# TapTempoMini.net
KiCad netlist of a schematic drawn in EAGLE
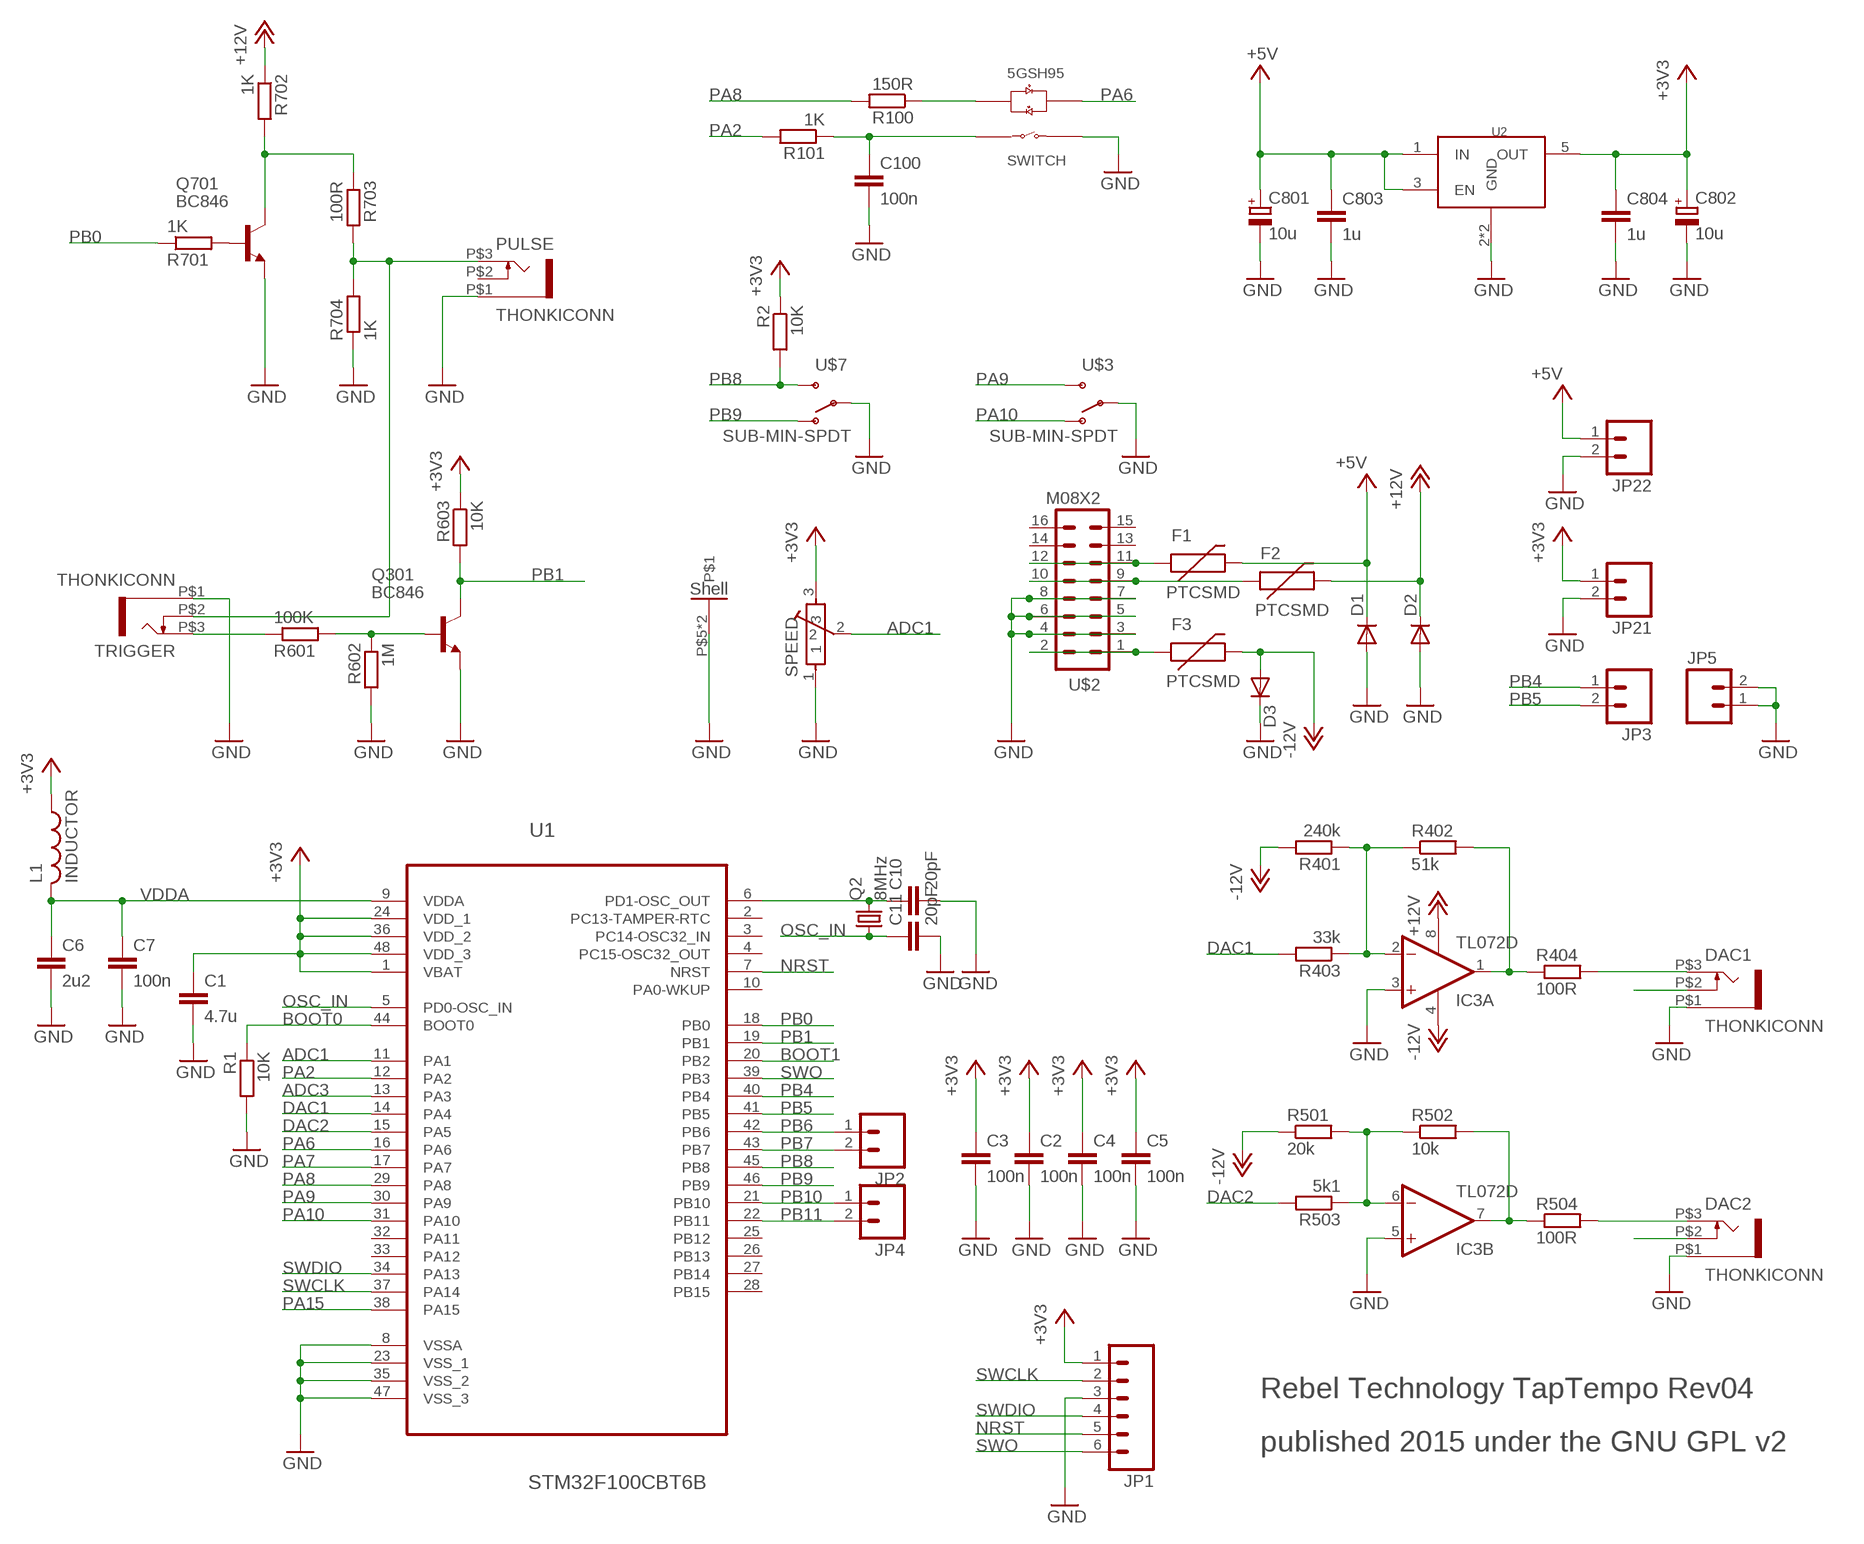
[diagram p0: schematic, sheet 1]

(export (version "E")
  (design (tool "Eeschema 10.0.6"))
  (components
    (comp (ref "C1")
      (value "4.7u")
      (footprint "eagle-import:C0603")
      (libsource (lib "eagle-import") (part "C-EUC0603"))
    )
    (comp (ref "C2")
      (value "100n")
      (footprint "eagle-import:C0603")
      (libsource (lib "eagle-import") (part "C-EUC0603"))
    )
    (comp (ref "C3")
      (value "100n")
      (footprint "eagle-import:C0603")
      (libsource (lib "eagle-import") (part "C-EUC0603"))
    )
    (comp (ref "C4")
      (value "100n")
      (footprint "eagle-import:C0603")
      (libsource (lib "eagle-import") (part "C-EUC0603"))
    )
    (comp (ref "C5")
      (value "100n")
      (footprint "eagle-import:C0603")
      (libsource (lib "eagle-import") (part "C-EUC0603"))
    )
    (comp (ref "C6")
      (value "2u2")
      (footprint "eagle-import:C0603")
      (libsource (lib "eagle-import") (part "C-EUC0603"))
    )
    (comp (ref "C7")
      (value "100n")
      (footprint "eagle-import:C0603")
      (libsource (lib "eagle-import") (part "C-EUC0603"))
    )
    (comp (ref "C10")
      (value "20pF")
      (footprint "eagle-import:C0603")
      (libsource (lib "eagle-import") (part "C-EUC0603"))
    )
    (comp (ref "C11")
      (value "20pF")
      (footprint "eagle-import:C0603")
      (libsource (lib "eagle-import") (part "C-EUC0603"))
    )
    (comp (ref "C100")
      (value "100n")
      (footprint "eagle-import:C0603")
      (libsource (lib "eagle-import") (part "C-EUC0603"))
    )
    (comp (ref "C801")
      (value "10u")
      (footprint "eagle-import:SANYO-OSCON_SMD_A5")
      (libsource (lib "eagle-import") (part "CPOL-EUSANYO_SMD_A5"))
    )
    (comp (ref "C802")
      (value "10u")
      (footprint "eagle-import:SANYO-OSCON_SMD_A5")
      (libsource (lib "eagle-import") (part "CPOL-EUSANYO_SMD_A5"))
    )
    (comp (ref "C803")
      (value "1u")
      (footprint "eagle-import:C0603")
      (libsource (lib "eagle-import") (part "C-EUC0603"))
    )
    (comp (ref "C804")
      (value "1u")
      (footprint "eagle-import:C0603")
      (libsource (lib "eagle-import") (part "C-EUC0603"))
    )
    (comp (ref "D1")
      (value "DIODESMA")
      (footprint "eagle-import:SMA-DIODE")
      (libsource (lib "eagle-import") (part "DIODESMA"))
    )
    (comp (ref "D2")
      (value "DIODESMA")
      (footprint "eagle-import:SMA-DIODE")
      (libsource (lib "eagle-import") (part "DIODESMA"))
    )
    (comp (ref "D3")
      (value "DIODESMA")
      (footprint "eagle-import:SMA-DIODE")
      (libsource (lib "eagle-import") (part "DIODESMA"))
    )
    (comp (ref "DAC1")
      (value "THONKICONN")
      (footprint "eagle-import:THONKICONN")
      (libsource (lib "eagle-import") (part "THONKICONN"))
    )
    (comp (ref "DAC2")
      (value "THONKICONN")
      (footprint "eagle-import:THONKICONN")
      (libsource (lib "eagle-import") (part "THONKICONN"))
    )
    (comp (ref "F1")
      (value "PTCSMD")
      (footprint "eagle-import:PTC-1206")
      (libsource (lib "eagle-import") (part "PTCSMD"))
    )
    (comp (ref "F2")
      (value "PTCSMD")
      (footprint "eagle-import:PTC-1206")
      (libsource (lib "eagle-import") (part "PTCSMD"))
    )
    (comp (ref "F3")
      (value "PTCSMD")
      (footprint "eagle-import:PTC-1206")
      (libsource (lib "eagle-import") (part "PTCSMD"))
    )
    (comp (ref "IC3")
      (value "TL072D")
      (footprint "eagle-import:SO08")
      (libsource (lib "eagle-import") (part "TL072D"))
    )
    (comp (ref "JP1")
      (value "M06SIP")
      (footprint "eagle-import:1X06")
      (libsource (lib "eagle-import") (part "M06SIP"))
    )
    (comp (ref "JP2")
      (value "M02PTH")
      (footprint "eagle-import:1X02")
      (libsource (lib "eagle-import") (part "M02PTH"))
    )
    (comp (ref "JP3")
      (value "M02PTH")
      (footprint "eagle-import:1X02")
      (libsource (lib "eagle-import") (part "M02PTH"))
    )
    (comp (ref "JP4")
      (value "M02PTH")
      (footprint "eagle-import:1X02")
      (libsource (lib "eagle-import") (part "M02PTH"))
    )
    (comp (ref "JP5")
      (value "M02PTH")
      (footprint "eagle-import:1X02")
      (libsource (lib "eagle-import") (part "M02PTH"))
    )
    (comp (ref "JP21")
      (value "M02PTH")
      (footprint "eagle-import:1X02")
      (libsource (lib "eagle-import") (part "M02PTH"))
    )
    (comp (ref "JP22")
      (value "M02PTH")
      (footprint "eagle-import:1X02")
      (libsource (lib "eagle-import") (part "M02PTH"))
    )
    (comp (ref "L1")
      (value "INDUCTOR")
      (footprint "eagle-import:0603")
      (libsource (lib "eagle-import") (part "INDUCTOR"))
    )
    (comp (ref "PULSE")
      (value "THONKICONN")
      (footprint "eagle-import:THONKICONN")
      (libsource (lib "eagle-import") (part "THONKICONN"))
    )
    (comp (ref "Q2")
      (value "8MHz")
      (footprint "eagle-import:HC49UP")
      (libsource (lib "eagle-import") (part "CRYSTALHC49UP"))
    )
    (comp (ref "Q301")
      (value "BC846")
      (footprint "eagle-import:SOT23")
      (libsource (lib "eagle-import") (part "BC846"))
    )
    (comp (ref "Q701")
      (value "BC846")
      (footprint "eagle-import:SOT23")
      (libsource (lib "eagle-import") (part "BC846"))
    )
    (comp (ref "R1")
      (value "10K")
      (footprint "eagle-import:R0603")
      (libsource (lib "eagle-import") (part "R-EU_R0603"))
    )
    (comp (ref "R2")
      (value "10K")
      (footprint "eagle-import:R0603")
      (libsource (lib "eagle-import") (part "R-EU_R0603"))
    )
    (comp (ref "R100")
      (value "150R")
      (footprint "eagle-import:0603")
      (libsource (lib "eagle-import") (part "R-EU_0603"))
    )
    (comp (ref "R101")
      (value "1K")
      (footprint "eagle-import:R0603")
      (libsource (lib "eagle-import") (part "R-EU_R0603"))
    )
    (comp (ref "R401")
      (value "240k")
      (footprint "eagle-import:R0603")
      (libsource (lib "eagle-import") (part "R-EU_R0603"))
    )
    (comp (ref "R402")
      (value "51k")
      (footprint "eagle-import:R0603")
      (libsource (lib "eagle-import") (part "R-EU_R0603"))
    )
    (comp (ref "R403")
      (value "33k")
      (footprint "eagle-import:R0603")
      (libsource (lib "eagle-import") (part "R-EU_R0603"))
    )
    (comp (ref "R404")
      (value "100R")
      (footprint "eagle-import:R0603")
      (libsource (lib "eagle-import") (part "R-EU_R0603"))
    )
    (comp (ref "R501")
      (value "20k")
      (footprint "eagle-import:R0603")
      (libsource (lib "eagle-import") (part "R-EU_R0603"))
    )
    (comp (ref "R502")
      (value "10k")
      (footprint "eagle-import:R0603")
      (libsource (lib "eagle-import") (part "R-EU_R0603"))
    )
    (comp (ref "R503")
      (value "5k1")
      (footprint "eagle-import:R0603")
      (libsource (lib "eagle-import") (part "R-EU_R0603"))
    )
    (comp (ref "R504")
      (value "100R")
      (footprint "eagle-import:R0603")
      (libsource (lib "eagle-import") (part "R-EU_R0603"))
    )
    (comp (ref "R601")
      (value "100K")
      (footprint "eagle-import:R0603")
      (libsource (lib "eagle-import") (part "R-EU_R0603"))
    )
    (comp (ref "R602")
      (value "1M")
      (footprint "eagle-import:R0603")
      (libsource (lib "eagle-import") (part "R-EU_R0603"))
    )
    (comp (ref "R603")
      (value "10K")
      (footprint "eagle-import:R0603")
      (libsource (lib "eagle-import") (part "R-EU_R0603"))
    )
    (comp (ref "R701")
      (value "1K")
      (footprint "eagle-import:R0603")
      (libsource (lib "eagle-import") (part "R-EU_R0603"))
    )
    (comp (ref "R702")
      (value "1K")
      (footprint "eagle-import:R0603")
      (libsource (lib "eagle-import") (part "R-EU_R0603"))
    )
    (comp (ref "R703")
      (value "100R")
      (footprint "eagle-import:R0603")
      (libsource (lib "eagle-import") (part "R-EU_R0603"))
    )
    (comp (ref "R704")
      (value "1K")
      (footprint "eagle-import:R0603")
      (libsource (lib "eagle-import") (part "R-EU_R0603"))
    )
    (comp (ref "SPEED")
      (value "POT-ALPS-RK09L1140")
      (footprint "eagle-import:POT-ALPS-RK09L1140")
      (libsource (lib "eagle-import") (part "POT-ALPS-RK09L1140"))
    )
    (comp (ref "TRIGGER")
      (value "THONKICONN")
      (footprint "eagle-import:THONKICONN")
      (libsource (lib "eagle-import") (part "THONKICONN"))
    )
    (comp (ref "U$1")
      (value "5GTH9")
      (footprint "eagle-import:5GTH9")
      (libsource (lib "eagle-import") (part "5GTH9"))
    )
    (comp (ref "U$2")
      (value "M08X2")
      (footprint "eagle-import:2X8")
      (libsource (lib "eagle-import") (part "M08X2"))
    )
    (comp (ref "U$3")
      (value "SUB-MIN-SPDT")
      (footprint "eagle-import:SUB-MIN-SPDT")
      (libsource (lib "eagle-import") (part "SUB-MIN-SPDT"))
    )
    (comp (ref "U$7")
      (value "SUB-MIN-SPDT")
      (footprint "eagle-import:SUB-MIN-SPDT")
      (libsource (lib "eagle-import") (part "SUB-MIN-SPDT"))
    )
    (comp (ref "U1")
      (value "STM32F100CBT6B")
      (footprint "eagle-import:QFP50P900X900X160-48N")
      (libsource (lib "eagle-import") (part "STM32F100CBT6B"))
    )
    (comp (ref "U2")
      (value "NCP702")
      (footprint "eagle-import:TSOP-5")
      (libsource (lib "eagle-import") (part "NCP702"))
    )
  )
  (nets
    (net (code "1") (name "+3V3") (class "Default")
      (node (ref "C1") (pin "1") (pinfunction "1_1") (pintype "passive"))
      (node (ref "C2") (pin "1") (pinfunction "1_1") (pintype "passive"))
      (node (ref "C3") (pin "1") (pinfunction "1_1") (pintype "passive"))
      (node (ref "C4") (pin "1") (pinfunction "1_1") (pintype "passive"))
      (node (ref "C5") (pin "1") (pinfunction "1_1") (pintype "passive"))
      (node (ref "C802") (pin "+") (pinfunction "+_+") (pintype "passive"))
      (node (ref "C804") (pin "1") (pinfunction "1_1") (pintype "passive"))
      (node (ref "JP1") (pin "1") (pinfunction "1_1") (pintype "passive"))
      (node (ref "JP21") (pin "1") (pinfunction "1_1") (pintype "passive"))
      (node (ref "L1") (pin "1") (pinfunction "1_1") (pintype "passive"))
      (node (ref "R2") (pin "1") (pinfunction "1_1") (pintype "passive"))
      (node (ref "R603") (pin "1") (pinfunction "1_1") (pintype "passive"))
      (node (ref "SPEED") (pin "3") (pinfunction "3_3") (pintype "bidirectional"))
      (node (ref "U1") (pin "1") (pinfunction "VBAT_1") (pintype "power_in"))
      (node (ref "U1") (pin "24") (pinfunction "VDD_1_24") (pintype "power_in"))
      (node (ref "U1") (pin "36") (pinfunction "VDD_2_36") (pintype "power_in"))
      (node (ref "U1") (pin "48") (pinfunction "VDD_3_48") (pintype "power_in"))
      (node (ref "U2") (pin "5") (pinfunction "OUT_5") (pintype "bidirectional"))
    )
    (net (code "2") (name "+5V") (class "Default")
      (node (ref "C801") (pin "+") (pinfunction "+_+") (pintype "passive"))
      (node (ref "C803") (pin "1") (pinfunction "1_1") (pintype "passive"))
      (node (ref "D1") (pin "C") (pinfunction "C_C") (pintype "passive"))
      (node (ref "F1") (pin "2") (pinfunction "2_2") (pintype "bidirectional"))
      (node (ref "JP22") (pin "1") (pinfunction "1_1") (pintype "passive"))
      (node (ref "U2") (pin "1") (pinfunction "IN_1") (pintype "bidirectional"))
      (node (ref "U2") (pin "3") (pinfunction "EN_3") (pintype "bidirectional"))
    )
    (net (code "3") (name "+12V") (class "Default")
      (node (ref "D2") (pin "C") (pinfunction "C_C") (pintype "passive"))
      (node (ref "F2") (pin "2") (pinfunction "2_2") (pintype "bidirectional"))
      (node (ref "IC3") (pin "8") (pinfunction "V+_8") (pintype "power_in"))
      (node (ref "R702") (pin "1") (pinfunction "1_1") (pintype "passive"))
    )
    (net (code "4") (name "-12V") (class "Default")
      (node (ref "D3") (pin "A") (pinfunction "A_A") (pintype "passive"))
      (node (ref "F3") (pin "2") (pinfunction "2_2") (pintype "bidirectional"))
      (node (ref "IC3") (pin "4") (pinfunction "V-_4") (pintype "power_in"))
      (node (ref "R401") (pin "2") (pinfunction "2_2") (pintype "passive"))
      (node (ref "R501") (pin "1") (pinfunction "1_1") (pintype "passive"))
    )
    (net (code "5") (name "/ADC1") (class "Default")
      (node (ref "SPEED") (pin "2") (pinfunction "2_2") (pintype "bidirectional"))
      (node (ref "U1") (pin "11") (pinfunction "PA1_11") (pintype "bidirectional"))
    )
    (net (code "6") (name "/ADC3") (class "Default")
      (node (ref "U1") (pin "13") (pinfunction "PA3_13") (pintype "bidirectional"))
    )
    (net (code "7") (name "/BOOT0") (class "Default")
      (node (ref "R1") (pin "1") (pinfunction "1_1") (pintype "passive"))
      (node (ref "U1") (pin "44") (pinfunction "BOOT0_44") (pintype "input"))
    )
    (net (code "8") (name "/BOOT1") (class "Default")
      (node (ref "U1") (pin "20") (pinfunction "PB2_20") (pintype "bidirectional"))
    )
    (net (code "9") (name "/DAC1") (class "Default")
      (node (ref "R403") (pin "2") (pinfunction "2_2") (pintype "passive"))
      (node (ref "U1") (pin "14") (pinfunction "PA4_14") (pintype "bidirectional"))
    )
    (net (code "10") (name "/DAC2") (class "Default")
      (node (ref "R503") (pin "2") (pinfunction "2_2") (pintype "passive"))
      (node (ref "U1") (pin "15") (pinfunction "PA5_15") (pintype "bidirectional"))
    )
    (net (code "11") (name "/NRST") (class "Default")
      (node (ref "JP1") (pin "5") (pinfunction "5_5") (pintype "passive"))
      (node (ref "U1") (pin "7") (pinfunction "NRST_7") (pintype "bidirectional"))
    )
    (net (code "12") (name "/OSC_IN") (class "Default")
      (node (ref "C11") (pin "1") (pinfunction "1_1") (pintype "passive"))
      (node (ref "Q2") (pin "1") (pinfunction "1_1") (pintype "passive"))
      (node (ref "U1") (pin "5") (pinfunction "PD0-OSC_IN_5") (pintype "input"))
    )
    (net (code "13") (name "/PA2") (class "Default")
      (node (ref "R101") (pin "2") (pinfunction "2_2") (pintype "passive"))
      (node (ref "U1") (pin "12") (pinfunction "PA2_12") (pintype "bidirectional"))
    )
    (net (code "14") (name "/PA6") (class "Default")
      (node (ref "U$1") (pin "+3") (pinfunction "LED_R+_+3") (pintype "input"))
      (node (ref "U1") (pin "16") (pinfunction "PA6_16") (pintype "bidirectional"))
    )
    (net (code "15") (name "/PA7") (class "Default")
      (node (ref "U1") (pin "17") (pinfunction "PA7_17") (pintype "bidirectional"))
    )
    (net (code "16") (name "/PA8") (class "Default")
      (node (ref "R100") (pin "2") (pinfunction "2_2") (pintype "passive"))
      (node (ref "U1") (pin "29") (pinfunction "PA8_29") (pintype "bidirectional"))
    )
    (net (code "17") (name "/PA9") (class "Default")
      (node (ref "U$3") (pin "3") (pinfunction "S_3") (pintype "passive"))
      (node (ref "U1") (pin "30") (pinfunction "PA9_30") (pintype "bidirectional"))
    )
    (net (code "18") (name "/PA10") (class "Default")
      (node (ref "U$3") (pin "1") (pinfunction "O_1") (pintype "passive"))
      (node (ref "U1") (pin "31") (pinfunction "PA10_31") (pintype "bidirectional"))
    )
    (net (code "19") (name "/PA15") (class "Default")
      (node (ref "U1") (pin "38") (pinfunction "PA15_38") (pintype "bidirectional"))
    )
    (net (code "20") (name "/PB0") (class "Default")
      (node (ref "R701") (pin "1") (pinfunction "1_1") (pintype "passive"))
      (node (ref "U1") (pin "18") (pinfunction "PB0_18") (pintype "bidirectional"))
    )
    (net (code "21") (name "/PB1") (class "Default")
      (node (ref "Q301") (pin "3") (pinfunction "C_3") (pintype "passive"))
      (node (ref "R603") (pin "2") (pinfunction "2_2") (pintype "passive"))
      (node (ref "U1") (pin "19") (pinfunction "PB1_19") (pintype "bidirectional"))
    )
    (net (code "22") (name "/PB4") (class "Default")
      (node (ref "JP3") (pin "1") (pinfunction "1_1") (pintype "passive"))
      (node (ref "U1") (pin "40") (pinfunction "PB4_40") (pintype "bidirectional"))
    )
    (net (code "23") (name "/PB5") (class "Default")
      (node (ref "JP3") (pin "2") (pinfunction "2_2") (pintype "passive"))
      (node (ref "U1") (pin "41") (pinfunction "PB5_41") (pintype "bidirectional"))
    )
    (net (code "24") (name "/PB6") (class "Default")
      (node (ref "JP2") (pin "1") (pinfunction "1_1") (pintype "passive"))
      (node (ref "U1") (pin "42") (pinfunction "PB6_42") (pintype "bidirectional"))
    )
    (net (code "25") (name "/PB7") (class "Default")
      (node (ref "JP2") (pin "2") (pinfunction "2_2") (pintype "passive"))
      (node (ref "U1") (pin "43") (pinfunction "PB7_43") (pintype "bidirectional"))
    )
    (net (code "26") (name "/PB8") (class "Default")
      (node (ref "R2") (pin "2") (pinfunction "2_2") (pintype "passive"))
      (node (ref "U$7") (pin "3") (pinfunction "S_3") (pintype "passive"))
      (node (ref "U1") (pin "45") (pinfunction "PB8_45") (pintype "bidirectional"))
    )
    (net (code "27") (name "/PB9") (class "Default")
      (node (ref "U$7") (pin "1") (pinfunction "O_1") (pintype "passive"))
      (node (ref "U1") (pin "46") (pinfunction "PB9_46") (pintype "bidirectional"))
    )
    (net (code "28") (name "/PB10") (class "Default")
      (node (ref "JP4") (pin "1") (pinfunction "1_1") (pintype "passive"))
      (node (ref "U1") (pin "21") (pinfunction "PB10_21") (pintype "bidirectional"))
    )
    (net (code "29") (name "/PB11") (class "Default")
      (node (ref "JP4") (pin "2") (pinfunction "2_2") (pintype "passive"))
      (node (ref "U1") (pin "22") (pinfunction "PB11_22") (pintype "bidirectional"))
    )
    (net (code "30") (name "/SWCLK") (class "Default")
      (node (ref "JP1") (pin "2") (pinfunction "2_2") (pintype "passive"))
      (node (ref "U1") (pin "37") (pinfunction "PA14_37") (pintype "bidirectional"))
    )
    (net (code "31") (name "/SWDIO") (class "Default")
      (node (ref "JP1") (pin "4") (pinfunction "4_4") (pintype "passive"))
      (node (ref "U1") (pin "34") (pinfunction "PA13_34") (pintype "bidirectional"))
    )
    (net (code "32") (name "/SWO") (class "Default")
      (node (ref "JP1") (pin "6") (pinfunction "6_6") (pintype "passive"))
      (node (ref "U1") (pin "39") (pinfunction "PB3_39") (pintype "bidirectional"))
    )
    (net (code "33") (name "/VDDA") (class "Default")
      (node (ref "C6") (pin "1") (pinfunction "1_1") (pintype "passive"))
      (node (ref "C7") (pin "1") (pinfunction "1_1") (pintype "passive"))
      (node (ref "L1") (pin "2") (pinfunction "2_2") (pintype "passive"))
      (node (ref "U1") (pin "9") (pinfunction "VDDA_9") (pintype "power_in"))
    )
    (net (code "34") (name "GND") (class "Default")
      (node (ref "C1") (pin "2") (pinfunction "2_2") (pintype "passive"))
      (node (ref "C10") (pin "2") (pinfunction "2_2") (pintype "passive"))
      (node (ref "C100") (pin "2") (pinfunction "2_2") (pintype "passive"))
      (node (ref "C11") (pin "2") (pinfunction "2_2") (pintype "passive"))
      (node (ref "C2") (pin "2") (pinfunction "2_2") (pintype "passive"))
      (node (ref "C3") (pin "2") (pinfunction "2_2") (pintype "passive"))
      (node (ref "C4") (pin "2") (pinfunction "2_2") (pintype "passive"))
      (node (ref "C5") (pin "2") (pinfunction "2_2") (pintype "passive"))
      (node (ref "C6") (pin "2") (pinfunction "2_2") (pintype "passive"))
      (node (ref "C7") (pin "2") (pinfunction "2_2") (pintype "passive"))
      (node (ref "C801") (pin "-") (pinfunction "-_-") (pintype "passive"))
      (node (ref "C802") (pin "-") (pinfunction "-_-") (pintype "passive"))
      (node (ref "C803") (pin "2") (pinfunction "2_2") (pintype "passive"))
      (node (ref "C804") (pin "2") (pinfunction "2_2") (pintype "passive"))
      (node (ref "D1") (pin "A") (pinfunction "A_A") (pintype "passive"))
      (node (ref "D2") (pin "A") (pinfunction "A_A") (pintype "passive"))
      (node (ref "D3") (pin "C") (pinfunction "C_C") (pintype "passive"))
      (node (ref "DAC1") (pin "P$1") (pinfunction "5_P$1") (pintype "passive"))
      (node (ref "DAC2") (pin "P$1") (pinfunction "5_P$1") (pintype "passive"))
      (node (ref "IC3") (pin "3") (pinfunction "+IN_3") (pintype "input"))
      (node (ref "IC3") (pin "5") (pinfunction "+IN_5") (pintype "input"))
      (node (ref "JP1") (pin "3") (pinfunction "3_3") (pintype "passive"))
      (node (ref "JP21") (pin "2") (pinfunction "2_2") (pintype "passive"))
      (node (ref "JP22") (pin "2") (pinfunction "2_2") (pintype "passive"))
      (node (ref "JP5") (pin "1") (pinfunction "1_1") (pintype "passive"))
      (node (ref "JP5") (pin "2") (pinfunction "2_2") (pintype "passive"))
      (node (ref "PULSE") (pin "P$1") (pinfunction "5_P$1") (pintype "passive"))
      (node (ref "Q301") (pin "2") (pinfunction "E_2") (pintype "passive"))
      (node (ref "Q701") (pin "2") (pinfunction "E_2") (pintype "passive"))
      (node (ref "R1") (pin "2") (pinfunction "2_2") (pintype "passive"))
      (node (ref "R602") (pin "2") (pinfunction "2_2") (pintype "passive"))
      (node (ref "R704") (pin "1") (pinfunction "1_1") (pintype "passive"))
      (node (ref "SPEED") (pin "1") (pinfunction "1_1") (pintype "bidirectional"))
      (node (ref "SPEED") (pin "P$5") (pinfunction "P$1_P$5") (pintype "bidirectional"))
      (node (ref "SPEED") (pin "P$6") (pinfunction "P$1_P$6") (pintype "bidirectional"))
      (node (ref "TRIGGER") (pin "P$1") (pinfunction "5_P$1") (pintype "passive"))
      (node (ref "U$1") (pin "1") (pinfunction "SWITCH_B_1") (pintype "power_in"))
      (node (ref "U$2") (pin "3") (pinfunction "3_3") (pintype "passive"))
      (node (ref "U$2") (pin "4") (pinfunction "4_4") (pintype "passive"))
      (node (ref "U$2") (pin "5") (pinfunction "5_5") (pintype "passive"))
      (node (ref "U$2") (pin "6") (pinfunction "6_6") (pintype "passive"))
      (node (ref "U$2") (pin "7") (pinfunction "7_7") (pintype "passive"))
      (node (ref "U$2") (pin "8") (pinfunction "8_8") (pintype "passive"))
      (node (ref "U$3") (pin "2") (pinfunction "P_2") (pintype "passive"))
      (node (ref "U$7") (pin "2") (pinfunction "P_2") (pintype "passive"))
      (node (ref "U1") (pin "23") (pinfunction "VSS_1_23") (pintype "power_in"))
      (node (ref "U1") (pin "35") (pinfunction "VSS_2_35") (pintype "power_in"))
      (node (ref "U1") (pin "47") (pinfunction "VSS_3_47") (pintype "power_in"))
      (node (ref "U1") (pin "8") (pinfunction "VSSA_8") (pintype "power_in"))
      (node (ref "U2") (pin "2") (pinfunction "GND_2") (pintype "bidirectional"))
      (node (ref "U2") (pin "4") (pinfunction "GND_4") (pintype "bidirectional"))
    )
    (net (code "35") (name "Net-(DAC1-3)") (class "Default")
      (node (ref "DAC1") (pin "P$3") (pinfunction "3_P$3") (pintype "passive"))
      (node (ref "R404") (pin "2") (pinfunction "2_2") (pintype "passive"))
    )
    (net (code "36") (name "Net-(DAC2-3)") (class "Default")
      (node (ref "DAC2") (pin "P$3") (pinfunction "3_P$3") (pintype "passive"))
      (node (ref "R504") (pin "2") (pinfunction "2_2") (pintype "passive"))
    )
    (net (code "37") (name "Net-(F1-Pad1)") (class "Default")
      (node (ref "F1") (pin "1") (pinfunction "1_1") (pintype "bidirectional"))
      (node (ref "U$2") (pin "11") (pinfunction "11_11") (pintype "passive"))
      (node (ref "U$2") (pin "12") (pinfunction "12_12") (pintype "passive"))
    )
    (net (code "38") (name "Net-(F2-Pad1)") (class "Default")
      (node (ref "F2") (pin "1") (pinfunction "1_1") (pintype "bidirectional"))
      (node (ref "U$2") (pin "10") (pinfunction "10_10") (pintype "passive"))
      (node (ref "U$2") (pin "9") (pinfunction "9_9") (pintype "passive"))
    )
    (net (code "39") (name "Net-(F3-Pad1)") (class "Default")
      (node (ref "F3") (pin "1") (pinfunction "1_1") (pintype "bidirectional"))
      (node (ref "U$2") (pin "1") (pinfunction "1_1") (pintype "passive"))
      (node (ref "U$2") (pin "2") (pinfunction "2_2") (pintype "passive"))
    )
    (net (code "40") (name "Net-(IC3A--IN)") (class "Default")
      (node (ref "IC3") (pin "2") (pinfunction "-IN_2") (pintype "input"))
      (node (ref "R401") (pin "1") (pinfunction "1_1") (pintype "passive"))
      (node (ref "R402") (pin "1") (pinfunction "1_1") (pintype "passive"))
      (node (ref "R403") (pin "1") (pinfunction "1_1") (pintype "passive"))
    )
    (net (code "41") (name "Net-(IC3A-OUT)") (class "Default")
      (node (ref "IC3") (pin "1") (pinfunction "OUT_1") (pintype "output"))
      (node (ref "R402") (pin "2") (pinfunction "2_2") (pintype "passive"))
      (node (ref "R404") (pin "1") (pinfunction "1_1") (pintype "passive"))
    )
    (net (code "42") (name "Net-(IC3B--IN)") (class "Default")
      (node (ref "IC3") (pin "6") (pinfunction "-IN_6") (pintype "input"))
      (node (ref "R501") (pin "2") (pinfunction "2_2") (pintype "passive"))
      (node (ref "R502") (pin "1") (pinfunction "1_1") (pintype "passive"))
      (node (ref "R503") (pin "1") (pinfunction "1_1") (pintype "passive"))
    )
    (net (code "43") (name "Net-(IC3B-OUT)") (class "Default")
      (node (ref "IC3") (pin "7") (pinfunction "OUT_7") (pintype "output"))
      (node (ref "R502") (pin "2") (pinfunction "2_2") (pintype "passive"))
      (node (ref "R504") (pin "1") (pinfunction "1_1") (pintype "passive"))
    )
    (net (code "44") (name "Net-(PULSE-3)") (class "Default")
      (node (ref "PULSE") (pin "P$3") (pinfunction "3_P$3") (pintype "passive"))
      (node (ref "R703") (pin "2") (pinfunction "2_2") (pintype "passive"))
      (node (ref "R704") (pin "2") (pinfunction "2_2") (pintype "passive"))
      (node (ref "TRIGGER") (pin "P$2") (pinfunction "4_P$2") (pintype "passive"))
    )
    (net (code "45") (name "Net-(Q301-B)") (class "Default")
      (node (ref "Q301") (pin "1") (pinfunction "B_1") (pintype "passive"))
      (node (ref "R601") (pin "2") (pinfunction "2_2") (pintype "passive"))
      (node (ref "R602") (pin "1") (pinfunction "1_1") (pintype "passive"))
    )
    (net (code "46") (name "Net-(Q701-B)") (class "Default")
      (node (ref "Q701") (pin "1") (pinfunction "B_1") (pintype "passive"))
      (node (ref "R701") (pin "2") (pinfunction "2_2") (pintype "passive"))
    )
    (net (code "47") (name "Net-(Q701-C)") (class "Default")
      (node (ref "Q701") (pin "3") (pinfunction "C_3") (pintype "passive"))
      (node (ref "R702") (pin "2") (pinfunction "2_2") (pintype "passive"))
      (node (ref "R703") (pin "1") (pinfunction "1_1") (pintype "passive"))
    )
    (net (code "48") (name "Net-(TRIGGER-3)") (class "Default")
      (node (ref "R601") (pin "1") (pinfunction "1_1") (pintype "passive"))
      (node (ref "TRIGGER") (pin "P$3") (pinfunction "3_P$3") (pintype "passive"))
    )
    (net (code "49") (name "Net-(U$1-LED_G+)") (class "Default")
      (node (ref "R100") (pin "1") (pinfunction "1_1") (pintype "passive"))
      (node (ref "U$1") (pin "-2") (pinfunction "LED_G+_-2") (pintype "input"))
    )
    (net (code "50") (name "Net-(U$1-SWITCH_A)") (class "Default")
      (node (ref "C100") (pin "1") (pinfunction "1_1") (pintype "passive"))
      (node (ref "R101") (pin "1") (pinfunction "1_1") (pintype "passive"))
      (node (ref "U$1") (pin "4") (pinfunction "SWITCH_A_4") (pintype "power_in"))
    )
    (net (code "51") (name "Net-(U1-PD1-OSC_OUT)") (class "Default")
      (node (ref "C10") (pin "1") (pinfunction "1_1") (pintype "passive"))
      (node (ref "Q2") (pin "2") (pinfunction "2_2") (pintype "passive"))
      (node (ref "U1") (pin "6") (pinfunction "PD1-OSC_OUT_6") (pintype "output"))
    )
    (net (code "52") (name "unconnected-(DAC1-4-PadP$2)") (class "Default")
      (node (ref "DAC1") (pin "P$2") (pinfunction "4_P$2") (pintype "passive"))
    )
    (net (code "53") (name "unconnected-(DAC2-4-PadP$2)") (class "Default")
      (node (ref "DAC2") (pin "P$2") (pinfunction "4_P$2") (pintype "passive"))
    )
    (net (code "54") (name "unconnected-(PULSE-4-PadP$2)") (class "Default")
      (node (ref "PULSE") (pin "P$2") (pinfunction "4_P$2") (pintype "passive"))
    )
    (net (code "55") (name "unconnected-(U$2-Pad13)") (class "Default")
      (node (ref "U$2") (pin "13") (pinfunction "13_13") (pintype "passive"))
    )
    (net (code "56") (name "unconnected-(U$2-Pad14)") (class "Default")
      (node (ref "U$2") (pin "14") (pinfunction "14_14") (pintype "passive"))
    )
    (net (code "57") (name "unconnected-(U$2-Pad15)") (class "Default")
      (node (ref "U$2") (pin "15") (pinfunction "15_15") (pintype "passive"))
    )
    (net (code "58") (name "unconnected-(U$2-Pad16)") (class "Default")
      (node (ref "U$2") (pin "16") (pinfunction "16_16") (pintype "passive"))
    )
    (net (code "59") (name "unconnected-(U1-PA0-WKUP-Pad10)") (class "Default")
      (node (ref "U1") (pin "10") (pinfunction "PA0-WKUP_10") (pintype "bidirectional"))
    )
    (net (code "60") (name "unconnected-(U1-PA11-Pad32)") (class "Default")
      (node (ref "U1") (pin "32") (pinfunction "PA11_32") (pintype "bidirectional"))
    )
    (net (code "61") (name "unconnected-(U1-PA12-Pad33)") (class "Default")
      (node (ref "U1") (pin "33") (pinfunction "PA12_33") (pintype "bidirectional"))
    )
    (net (code "62") (name "unconnected-(U1-PB12-Pad25)") (class "Default")
      (node (ref "U1") (pin "25") (pinfunction "PB12_25") (pintype "bidirectional"))
    )
    (net (code "63") (name "unconnected-(U1-PB13-Pad26)") (class "Default")
      (node (ref "U1") (pin "26") (pinfunction "PB13_26") (pintype "bidirectional"))
    )
    (net (code "64") (name "unconnected-(U1-PB14-Pad27)") (class "Default")
      (node (ref "U1") (pin "27") (pinfunction "PB14_27") (pintype "bidirectional"))
    )
    (net (code "65") (name "unconnected-(U1-PB15-Pad28)") (class "Default")
      (node (ref "U1") (pin "28") (pinfunction "PB15_28") (pintype "bidirectional"))
    )
    (net (code "66") (name "unconnected-(U1-PC13-TAMPER-RTC-Pad2)") (class "Default")
      (node (ref "U1") (pin "2") (pinfunction "PC13-TAMPER-RTC_2") (pintype "bidirectional"))
    )
    (net (code "67") (name "unconnected-(U1-PC14-OSC32_IN-Pad3)") (class "Default")
      (node (ref "U1") (pin "3") (pinfunction "PC14-OSC32_IN_3") (pintype "bidirectional"))
    )
    (net (code "68") (name "unconnected-(U1-PC15-OSC32_OUT-Pad4)") (class "Default")
      (node (ref "U1") (pin "4") (pinfunction "PC15-OSC32_OUT_4") (pintype "bidirectional"))
    )
  )
)
